# USB_to_UART.net
KiCad netlist of a schematic drawn in Altium Designer
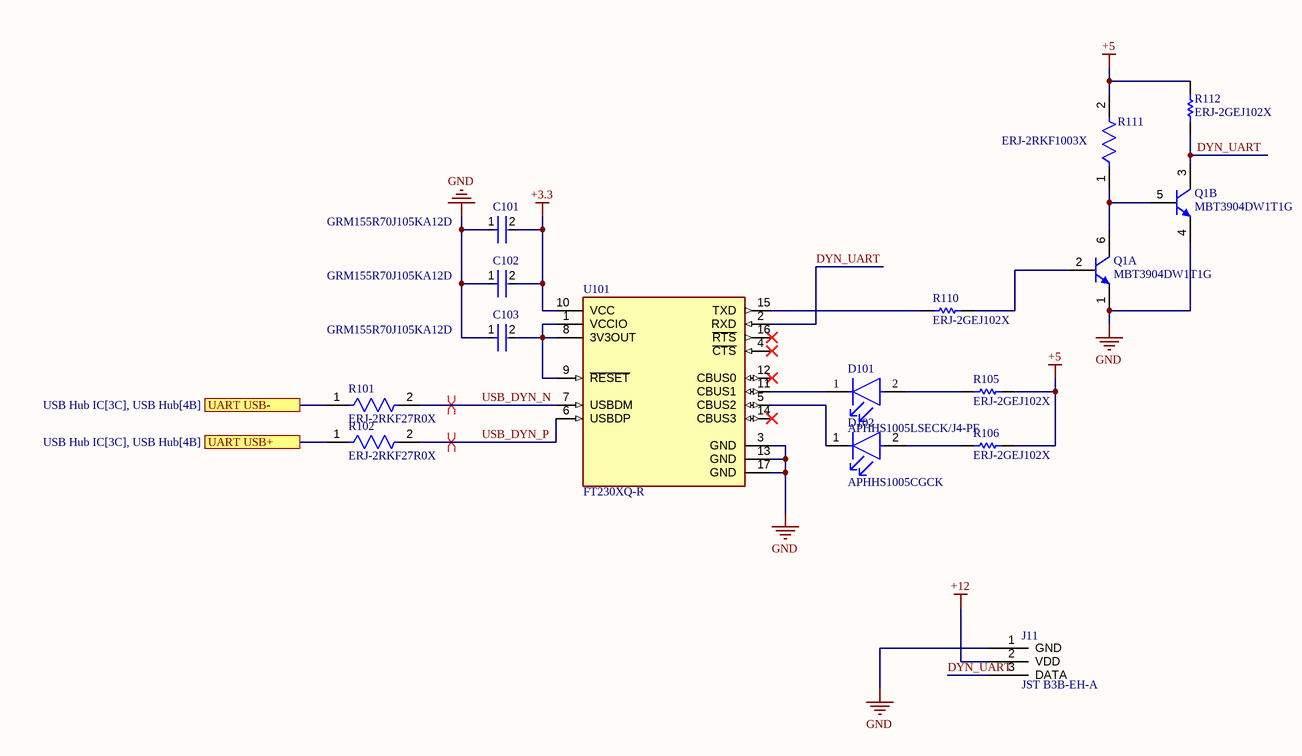
[diagram p0: USB to UART.SchDoc]

(export (version "E")
  (design (tool "Eeschema 10.0.6"))
  (components
    (comp (ref "C101")
      (value "GRM155R70J105KA12D")
      (footprint "FP-GRM155-0_05-MFG")
      (description "Chip Multilayer Ceramic Capacitors for General Purpose, 0402, 1.0uF, X7R, 15%, 10%, 6.3V")
      (fields (field (name "TOLERANCE") "10%"))
      (libsource (lib "Altium Content Vault") (part "02cd4be3c70576c341d710602a673aa"))
    )
    (comp (ref "C102")
      (value "GRM155R70J105KA12D")
      (footprint "FP-GRM155-0_05-MFG")
      (description "Chip Multilayer Ceramic Capacitors for General Purpose, 0402, 1.0uF, X7R, 15%, 10%, 6.3V")
      (fields (field (name "TOLERANCE") "10%"))
      (libsource (lib "Altium Content Vault") (part "02cd4be3c70576c341d710602a673aa"))
    )
    (comp (ref "C103")
      (value "GRM155R70J105KA12D")
      (footprint "FP-GRM155-0_05-MFG")
      (description "Chip Multilayer Ceramic Capacitors for General Purpose, 0402, 1.0uF, X7R, 15%, 10%, 6.3V")
      (fields (field (name "TOLERANCE") "10%"))
      (libsource (lib "Altium Content Vault") (part "02cd4be3c70576c341d710602a673aa"))
    )
    (comp (ref "D101")
      (value "APHHS1005LSECK/J4-PF")
      (footprint "FP-APHHS1005LSECK-J4-PF-MFG")
      (description "APHHS1005LSECK/J4-PF LED Uni-Color SB. Orange 611nm 2-Pin SMD T/R")
      (libsource (lib "Altium Content Vault") (part "8706943c75ba83719d021d2fdc84c58"))
    )
    (comp (ref "D102")
      (value "APHHS1005CGCK")
      (footprint "FP-APHHS1005CGCK-MFG")
      (description "LED GREEN CLEAR CHIP SMD")
      (libsource (lib "Altium Content Vault") (part "8706943c75ba83719d021d2fdc84c58"))
    )
    (comp (ref "J11")
      (value "JST B3B-EH-A")
      (footprint "JST B3B-EH-A")
      (libsource (lib "Schlib1") (part "JST B3B-EH-A"))
    )
    (comp (ref "Q1")
      (value "MBT3904DW1T1G")
      (footprint "ONSC-SOT-363-6-419B-02_W_V")
      (description "Dual General Purpose Transistors, 6-Pin SOT-363, Pb-Free, Tape and Reel")
      (fields (field (name "MANUFACTURER") "On Semiconductor"))
      (libsource (lib "Altium Content Vault") (part "ONSC-NPN_NPN-6_F"))
    )
    (comp (ref "R101")
      (value "ERJ-2RKF27R0X")
      (footprint "FP-ERJ2R-IPC_B")
      (description "RES SMD 27 OHM 1% 1/10W 0402")
      (fields (field (name "TOLERANCE") "1%"))
      (libsource (lib "Altium Content Vault") (part "8db39607336c341a927600551d01821"))
    )
    (comp (ref "R102")
      (value "ERJ-2RKF27R0X")
      (footprint "FP-ERJ2R-IPC_B")
      (description "RES SMD 27 OHM 1% 1/10W 0402")
      (fields (field (name "TOLERANCE") "1%"))
      (libsource (lib "Altium Content Vault") (part "8db39607336c341a927600551d01821"))
    )
    (comp (ref "R105")
      (value "ERJ-2GEJ102X")
      (footprint "RESC1005X40X25NL05T05")
      (fields (field (name "MANUFACTURER") "Panasonic"))
      (libsource (lib "Altium Content Vault") (part "RES"))
    )
    (comp (ref "R106")
      (value "ERJ-2GEJ102X")
      (footprint "RESC1005X40X25NL05T05")
      (fields (field (name "MANUFACTURER") "Panasonic"))
      (libsource (lib "Altium Content Vault") (part "RES"))
    )
    (comp (ref "R110")
      (value "ERJ-2GEJ102X")
      (footprint "RESC1005X40X25NL05T05")
      (fields (field (name "MANUFACTURER") "Panasonic"))
      (libsource (lib "Altium Content Vault") (part "RES"))
    )
    (comp (ref "R111")
      (value "ERJ-2RKF1003X")
      (footprint "FP-ERJ2RK-IPC_C")
      (description "RES SMD 100K OHM 1% 1/10W 0402")
      (fields (field (name "TOLERANCE") "1%"))
      (libsource (lib "Altium Content Vault") (part "1029c3af85768c4190bb7ad29bc67b5"))
    )
    (comp (ref "R112")
      (value "ERJ-2GEJ102X")
      (footprint "RESC1005X40X25NL05T05")
      (fields (field (name "MANUFACTURER") "Panasonic"))
      (libsource (lib "Altium Content Vault") (part "RES"))
    )
    (comp (ref "U101")
      (value "FT230XQ-R")
      (footprint "FP-QFN-16-MFG")
      (description "IC USB SERIAL BASIC UART 16QFN")
      (libsource (lib "Altium Content Vault") (part "29d2eb9587eff32afae5da052de4085"))
    )
  )
  (nets
    (net (code "1") (name "+3.3") (class "Default")
      (node (ref "C101") (pin "2") (pinfunction "2_2") (pintype "passive"))
      (node (ref "C102") (pin "2") (pinfunction "2_2") (pintype "passive"))
      (node (ref "U101") (pin "10") (pinfunction "VCC_10") (pintype "power_in"))
    )
    (net (code "2") (name "+5") (class "Default")
      (node (ref "R105") (pin "2") (pinfunction "2_2") (pintype "passive"))
      (node (ref "R106") (pin "2") (pinfunction "2_2") (pintype "passive"))
      (node (ref "R111") (pin "2") (pinfunction "2_2") (pintype "passive"))
      (node (ref "R112") (pin "2") (pinfunction "2_2") (pintype "passive"))
    )
    (net (code "3") (name "+12") (class "Default")
      (node (ref "J11") (pin "2") (pinfunction "VDD_2") (pintype "passive"))
    )
    (net (code "4") (name "/DYN_UART") (class "Default")
      (node (ref "J11") (pin "3") (pinfunction "DATA_3") (pintype "passive"))
      (node (ref "Q1") (pin "3") (pinfunction "C_3") (pintype "passive"))
      (node (ref "R112") (pin "1") (pinfunction "1_1") (pintype "passive"))
      (node (ref "U101") (pin "2") (pinfunction "RXD_2") (pintype "input"))
    )
    (net (code "5") (name "/UART USB+") (class "Default")
      (node (ref "R102") (pin "1") (pinfunction "1_1") (pintype "passive"))
    )
    (net (code "6") (name "/UART USB-") (class "Default")
      (node (ref "R101") (pin "1") (pinfunction "1_1") (pintype "passive"))
    )
    (net (code "7") (name "/USB_DYN_N") (class "Default")
      (node (ref "R101") (pin "2") (pinfunction "2_2") (pintype "passive"))
      (node (ref "U101") (pin "7") (pinfunction "USBDM_7") (pintype "input"))
    )
    (net (code "8") (name "/USB_DYN_P") (class "Default")
      (node (ref "R102") (pin "2") (pinfunction "2_2") (pintype "passive"))
      (node (ref "U101") (pin "6") (pinfunction "USBDP_6") (pintype "input"))
    )
    (net (code "9") (name "GND") (class "Default")
      (node (ref "C101") (pin "1") (pinfunction "1_1") (pintype "passive"))
      (node (ref "C102") (pin "1") (pinfunction "1_1") (pintype "passive"))
      (node (ref "C103") (pin "1") (pinfunction "1_1") (pintype "passive"))
      (node (ref "J11") (pin "1") (pinfunction "GND_1") (pintype "passive"))
      (node (ref "Q1") (pin "1") (pinfunction "E_1") (pintype "passive"))
      (node (ref "Q1") (pin "4") (pinfunction "E_4") (pintype "passive"))
      (node (ref "U101") (pin "13") (pinfunction "GND_13") (pintype "power_in"))
      (node (ref "U101") (pin "17") (pinfunction "GND_17") (pintype "power_in"))
      (node (ref "U101") (pin "3") (pinfunction "GND_3") (pintype "power_in"))
    )
    (net (code "10") (name "Net-(D101-A)") (class "Default")
      (node (ref "D101") (pin "2") (pinfunction "A_2") (pintype "passive"))
      (node (ref "R105") (pin "1") (pinfunction "1_1") (pintype "passive"))
    )
    (net (code "11") (name "Net-(D101-C)") (class "Default")
      (node (ref "D101") (pin "1") (pinfunction "C_1") (pintype "passive"))
      (node (ref "U101") (pin "11") (pinfunction "CBUS1_11") (pintype "bidirectional"))
    )
    (net (code "12") (name "Net-(D102-A)") (class "Default")
      (node (ref "D102") (pin "2") (pinfunction "A_2") (pintype "passive"))
      (node (ref "R106") (pin "1") (pinfunction "1_1") (pintype "passive"))
    )
    (net (code "13") (name "Net-(D102-C)") (class "Default")
      (node (ref "D102") (pin "1") (pinfunction "C_1") (pintype "passive"))
      (node (ref "U101") (pin "5") (pinfunction "CBUS2_5") (pintype "bidirectional"))
    )
    (net (code "14") (name "Net-(Q1A-B)") (class "Default")
      (node (ref "Q1") (pin "2") (pinfunction "B_2") (pintype "passive"))
      (node (ref "R110") (pin "2") (pinfunction "2_2") (pintype "passive"))
    )
    (net (code "15") (name "Net-(Q1A-C)") (class "Default")
      (node (ref "Q1") (pin "5") (pinfunction "B_5") (pintype "passive"))
      (node (ref "Q1") (pin "6") (pinfunction "C_6") (pintype "passive"))
      (node (ref "R111") (pin "1") (pinfunction "1_1") (pintype "passive"))
    )
    (net (code "16") (name "Net-(U101-3V3OUT)") (class "Default")
      (node (ref "C103") (pin "2") (pinfunction "2_2") (pintype "passive"))
      (node (ref "U101") (pin "1") (pinfunction "VCCIO_1") (pintype "power_in"))
      (node (ref "U101") (pin "8") (pinfunction "3V3OUT_8") (pintype "power_in"))
      (node (ref "U101") (pin "9") (pinfunction "~{RESET}_9") (pintype "input"))
    )
    (net (code "17") (name "Net-(U101-TXD)") (class "Default")
      (node (ref "R110") (pin "1") (pinfunction "1_1") (pintype "passive"))
      (node (ref "U101") (pin "15") (pinfunction "TXD_15") (pintype "output"))
    )
    (net (code "18") (name "unconnected-(U101-CBUS0-Pad12)") (class "Default")
      (node (ref "U101") (pin "12") (pinfunction "CBUS0_12") (pintype "bidirectional+no_connect"))
    )
    (net (code "19") (name "unconnected-(U101-CBUS3-Pad14)") (class "Default")
      (node (ref "U101") (pin "14") (pinfunction "CBUS3_14") (pintype "bidirectional+no_connect"))
    )
    (net (code "20") (name "unconnected-(U101-~{CTS}-Pad4)") (class "Default")
      (node (ref "U101") (pin "4") (pinfunction "~{CTS}_4") (pintype "input+no_connect"))
    )
    (net (code "21") (name "unconnected-(U101-~{RTS}-Pad16)") (class "Default")
      (node (ref "U101") (pin "16") (pinfunction "~{RTS}_16") (pintype "output+no_connect"))
    )
  )
)
